# PSU.net
KiCad netlist of a schematic drawn in Altium Designer
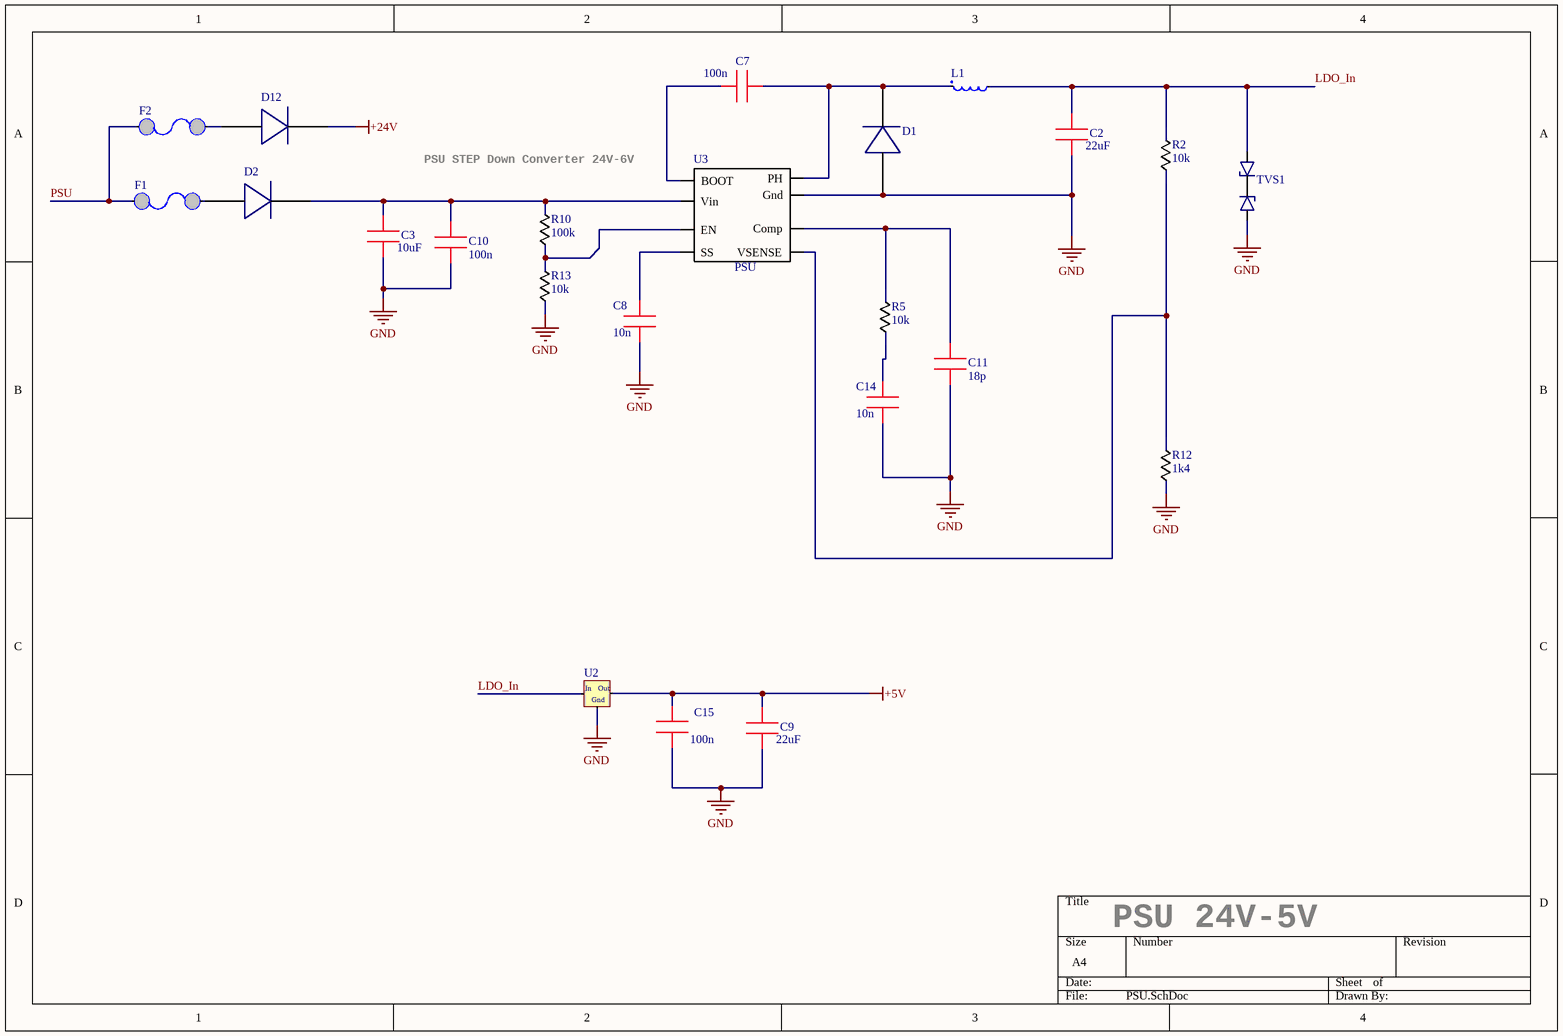
[diagram p0: PSU.SchDoc]

(export (version "E")
  (design (tool "Eeschema 10.0.6"))
  (components
    (comp (ref "C2")
      (value "22uF")
      (footprint "1206_CAP")
      (fields (field (name "PART NUMBER") "CC1206KKX5R7BB226"))
      (libsource (lib "kontr") (part "0805 Cap"))
    )
    (comp (ref "C3")
      (value "10uF")
      (footprint "1206_CAP")
      (fields (field (name "PART NUMBER") "CC1206KKX5R9BB106"))
      (libsource (lib "kontr") (part "0805 Cap"))
    )
    (comp (ref "C7")
      (value "100n")
      (footprint "0603_Cap")
      (fields (field (name "PART NUMBER") "CC0603ZRY5V9BB104"))
      (libsource (lib "kontr") (part "0805 Cap"))
    )
    (comp (ref "C8")
      (value "10n")
      (footprint "0603_Cap")
      (fields (field (name "PART NUMBER") "CC0603ZRY5V9BB103"))
      (libsource (lib "kontr") (part "0805 Cap"))
    )
    (comp (ref "C9")
      (value "22uF")
      (footprint "1206_CAP")
      (fields (field (name "PART NUMBER") "CC1206KKX5R7BB226"))
      (libsource (lib "kontr") (part "0805 Cap"))
    )
    (comp (ref "C10")
      (value "100n")
      (footprint "0603_Cap")
      (fields (field (name "PART NUMBER") "CC0603ZRY5V9BB104"))
      (libsource (lib "kontr") (part "0805 Cap"))
    )
    (comp (ref "C11")
      (value "18p")
      (footprint "0603_Cap")
      (fields (field (name "PART NUMBER") "CC0603JRNPO9BN180"))
      (libsource (lib "kontr") (part "0603 CAP"))
    )
    (comp (ref "C14")
      (value "10n")
      (footprint "0603_Cap")
      (fields (field (name "PART NUMBER") "CC0603ZRY5V9BB103"))
      (libsource (lib "kontr") (part "0805 Cap"))
    )
    (comp (ref "C15")
      (value "100n")
      (footprint "0603_Cap")
      (fields (field (name "PART NUMBER") "CC0603ZRY5V9BB104"))
      (libsource (lib "kontr") (part "Capasitor 0805"))
    )
    (comp (ref "D1")
      (value "~")
      (footprint "B340A-13-F")
      (fields (field (name "PART NUMBER") "B340A-13-F"))
      (libsource (lib "kontr") (part "B340A-13-F"))
    )
    (comp (ref "D2")
      (value "~")
      (footprint "B340A-13-F")
      (fields (field (name "PART NUMBER") "Schottky Diode 40V 3A"))
      (libsource (lib "kontr") (part "B340A-13-F"))
    )
    (comp (ref "D12")
      (value "~")
      (footprint "B340A-13-F")
      (fields (field (name "PART NUMBER") "B340A-13-F"))
      (libsource (lib "kontr") (part "B340A-13-F"))
    )
    (comp (ref "F1")
      (value "~")
      (footprint "Fuse USMF030")
      (fields (field (name "PART NUMBER") "MF-MSMF030-2"))
      (libsource (lib "kontr") (part "Fuse PTS"))
    )
    (comp (ref "F2")
      (value "~")
      (footprint "Fuse USMF030")
      (fields (field (name "PART NUMBER") "MF-MSMF030-2"))
      (libsource (lib "kontr") (part "Fuse PTS"))
    )
    (comp (ref "L1")
      (value "~")
      (footprint "CDRH127/LDNP-270MC,")
      (fields (field (name "PART NUMBER") "CDRH127/LDNP-220MC"))
      (libsource (lib "kontr") (part "CDRH127/LDNP-270MC"))
    )
    (comp (ref "R2")
      (value "10k")
      (footprint "0603_Res")
      (fields (field (name "PART NUMBER") "RT0603FRE0710KL"))
      (libsource (lib "kontr") (part "Resistor 0805"))
    )
    (comp (ref "R5")
      (value "10k")
      (footprint "0603_Res")
      (fields (field (name "PART NUMBER") "RT0603FRE0710KL"))
      (libsource (lib "kontr") (part "Resistor 0805"))
    )
    (comp (ref "R10")
      (value "100k")
      (footprint "0603_Res")
      (fields (field (name "PART NUMBER") "RC0603FR-07100KL"))
      (libsource (lib "kontr") (part "Resistor 0805"))
    )
    (comp (ref "R12")
      (value "1k4")
      (footprint "0603_Res")
      (fields (field (name "PART NUMBER") "RC0603FR-071K4L"))
      (libsource (lib "kontr") (part "Resistor 0805"))
    )
    (comp (ref "R13")
      (value "10k")
      (footprint "0603_Res")
      (fields (field (name "PART NUMBER") "RT0603FRE0710KL"))
      (libsource (lib "kontr") (part "Resistor 0805"))
    )
    (comp (ref "TVS1")
      (value "TVS Diode")
      (footprint "SM6T")
      (fields (field (name "PART NUMBER") "SM6T12CA"))
      (libsource (lib "kontr") (part "SM6T12CA"))
    )
    (comp (ref "U2")
      (value "~")
      (footprint "SOT223")
      (fields (field (name "PART NUMBER") "LM1117MPX-5.0"))
      (libsource (lib "kontr") (part "NCV1117ST50T3G"))
    )
    (comp (ref "U3")
      (value "PSU")
      (footprint "SOIC 8")
      (fields (field (name "PART NUMBER") "TPS54331DR"))
      (libsource (lib "kontr") (part "TPS54331"))
    )
  )
  (nets
    (net (code "1") (name "+5V") (class "Default")
      (node (ref "C15") (pin "1") (pinfunction "1_1") (pintype "passive"))
      (node (ref "C9") (pin "2") (pinfunction "2_2") (pintype "passive"))
      (node (ref "U2") (pin "2") (pinfunction "OUT_2") (pintype "passive"))
    )
    (net (code "2") (name "+24V") (class "Default")
      (node (ref "D12") (pin "1") (pinfunction "1_1") (pintype "passive"))
    )
    (net (code "3") (name "/LDO_In") (class "Default")
      (node (ref "C2") (pin "2") (pinfunction "2_2") (pintype "passive"))
      (node (ref "L1") (pin "2") (pinfunction "2_2") (pintype "passive"))
      (node (ref "R2") (pin "2") (pintype "passive"))
      (node (ref "TVS1") (pin "2") (pinfunction "2_2") (pintype "passive"))
      (node (ref "U2") (pin "3") (pinfunction "IN_3") (pintype "passive"))
    )
    (net (code "4") (name "/PSU") (class "Default")
      (node (ref "F1") (pin "1") (pinfunction "1_1") (pintype "passive"))
      (node (ref "F2") (pin "1") (pinfunction "1_1") (pintype "passive"))
    )
    (net (code "5") (name "GND") (class "Default")
      (node (ref "C10") (pin "1") (pinfunction "1_1") (pintype "passive"))
      (node (ref "C11") (pin "1") (pinfunction "1_1") (pintype "passive"))
      (node (ref "C14") (pin "1") (pinfunction "1_1") (pintype "passive"))
      (node (ref "C15") (pin "2") (pinfunction "2_2") (pintype "passive"))
      (node (ref "C2") (pin "1") (pinfunction "1_1") (pintype "passive"))
      (node (ref "C3") (pin "1") (pinfunction "1_1") (pintype "passive"))
      (node (ref "C8") (pin "1") (pinfunction "1_1") (pintype "passive"))
      (node (ref "C9") (pin "1") (pinfunction "1_1") (pintype "passive"))
      (node (ref "D1") (pin "2") (pinfunction "1_2") (pintype "passive"))
      (node (ref "R12") (pin "1") (pintype "passive"))
      (node (ref "R13") (pin "1") (pintype "passive"))
      (node (ref "TVS1") (pin "1") (pinfunction "1_1") (pintype "passive"))
      (node (ref "U2") (pin "1") (pinfunction "GND_1") (pintype "passive"))
      (node (ref "U3") (pin "7") (pinfunction "Gnd_7") (pintype "passive"))
    )
    (net (code "6") (name "Net-(C14-Pad2)") (class "Default")
      (node (ref "C14") (pin "2") (pinfunction "2_2") (pintype "passive"))
      (node (ref "R5") (pin "1") (pintype "passive"))
    )
    (net (code "7") (name "Net-(D2-1-Pad2)") (class "Default")
      (node (ref "D2") (pin "2") (pinfunction "1_2") (pintype "passive"))
      (node (ref "F1") (pin "0") (pinfunction "0_0") (pintype "passive"))
    )
    (net (code "8") (name "Net-(D12-1-Pad2)") (class "Default")
      (node (ref "D12") (pin "2") (pinfunction "1_2") (pintype "passive"))
      (node (ref "F2") (pin "0") (pinfunction "0_0") (pintype "passive"))
    )
    (net (code "9") (name "Net-(U3-BOOT)") (class "Default")
      (node (ref "C7") (pin "1") (pinfunction "1_1") (pintype "passive"))
      (node (ref "U3") (pin "1") (pinfunction "BOOT_1") (pintype "passive"))
    )
    (net (code "10") (name "Net-(U3-Comp)") (class "Default")
      (node (ref "C11") (pin "2") (pinfunction "2_2") (pintype "passive"))
      (node (ref "R5") (pin "2") (pintype "passive"))
      (node (ref "U3") (pin "6") (pinfunction "Comp_6") (pintype "passive"))
    )
    (net (code "11") (name "Net-(U3-EN)") (class "Default")
      (node (ref "R10") (pin "1") (pintype "passive"))
      (node (ref "R13") (pin "2") (pintype "passive"))
      (node (ref "U3") (pin "3") (pinfunction "EN_3") (pintype "passive"))
    )
    (net (code "12") (name "Net-(U3-PH)") (class "Default")
      (node (ref "C7") (pin "2") (pinfunction "2_2") (pintype "passive"))
      (node (ref "D1") (pin "1") (pinfunction "1_1") (pintype "passive"))
      (node (ref "L1") (pin "1") (pinfunction "1_1") (pintype "passive"))
      (node (ref "U3") (pin "8") (pinfunction "PH_8") (pintype "passive"))
    )
    (net (code "13") (name "Net-(U3-SS)") (class "Default")
      (node (ref "C8") (pin "2") (pinfunction "2_2") (pintype "passive"))
      (node (ref "U3") (pin "4") (pinfunction "SS_4") (pintype "passive"))
    )
    (net (code "14") (name "Net-(U3-VSENSE)") (class "Default")
      (node (ref "R12") (pin "2") (pintype "passive"))
      (node (ref "R2") (pin "1") (pintype "passive"))
      (node (ref "U3") (pin "5") (pinfunction "VSENSE_5") (pintype "passive"))
    )
    (net (code "15") (name "Net-(U3-Vin)") (class "Default")
      (node (ref "C10") (pin "2") (pinfunction "2_2") (pintype "passive"))
      (node (ref "C3") (pin "2") (pinfunction "2_2") (pintype "passive"))
      (node (ref "D2") (pin "1") (pinfunction "1_1") (pintype "passive"))
      (node (ref "R10") (pin "2") (pintype "passive"))
      (node (ref "U3") (pin "2") (pinfunction "Vin_2") (pintype "passive"))
    )
  )
)
